# RF1_RS485v5.net
KiCad netlist of a schematic drawn in EAGLE
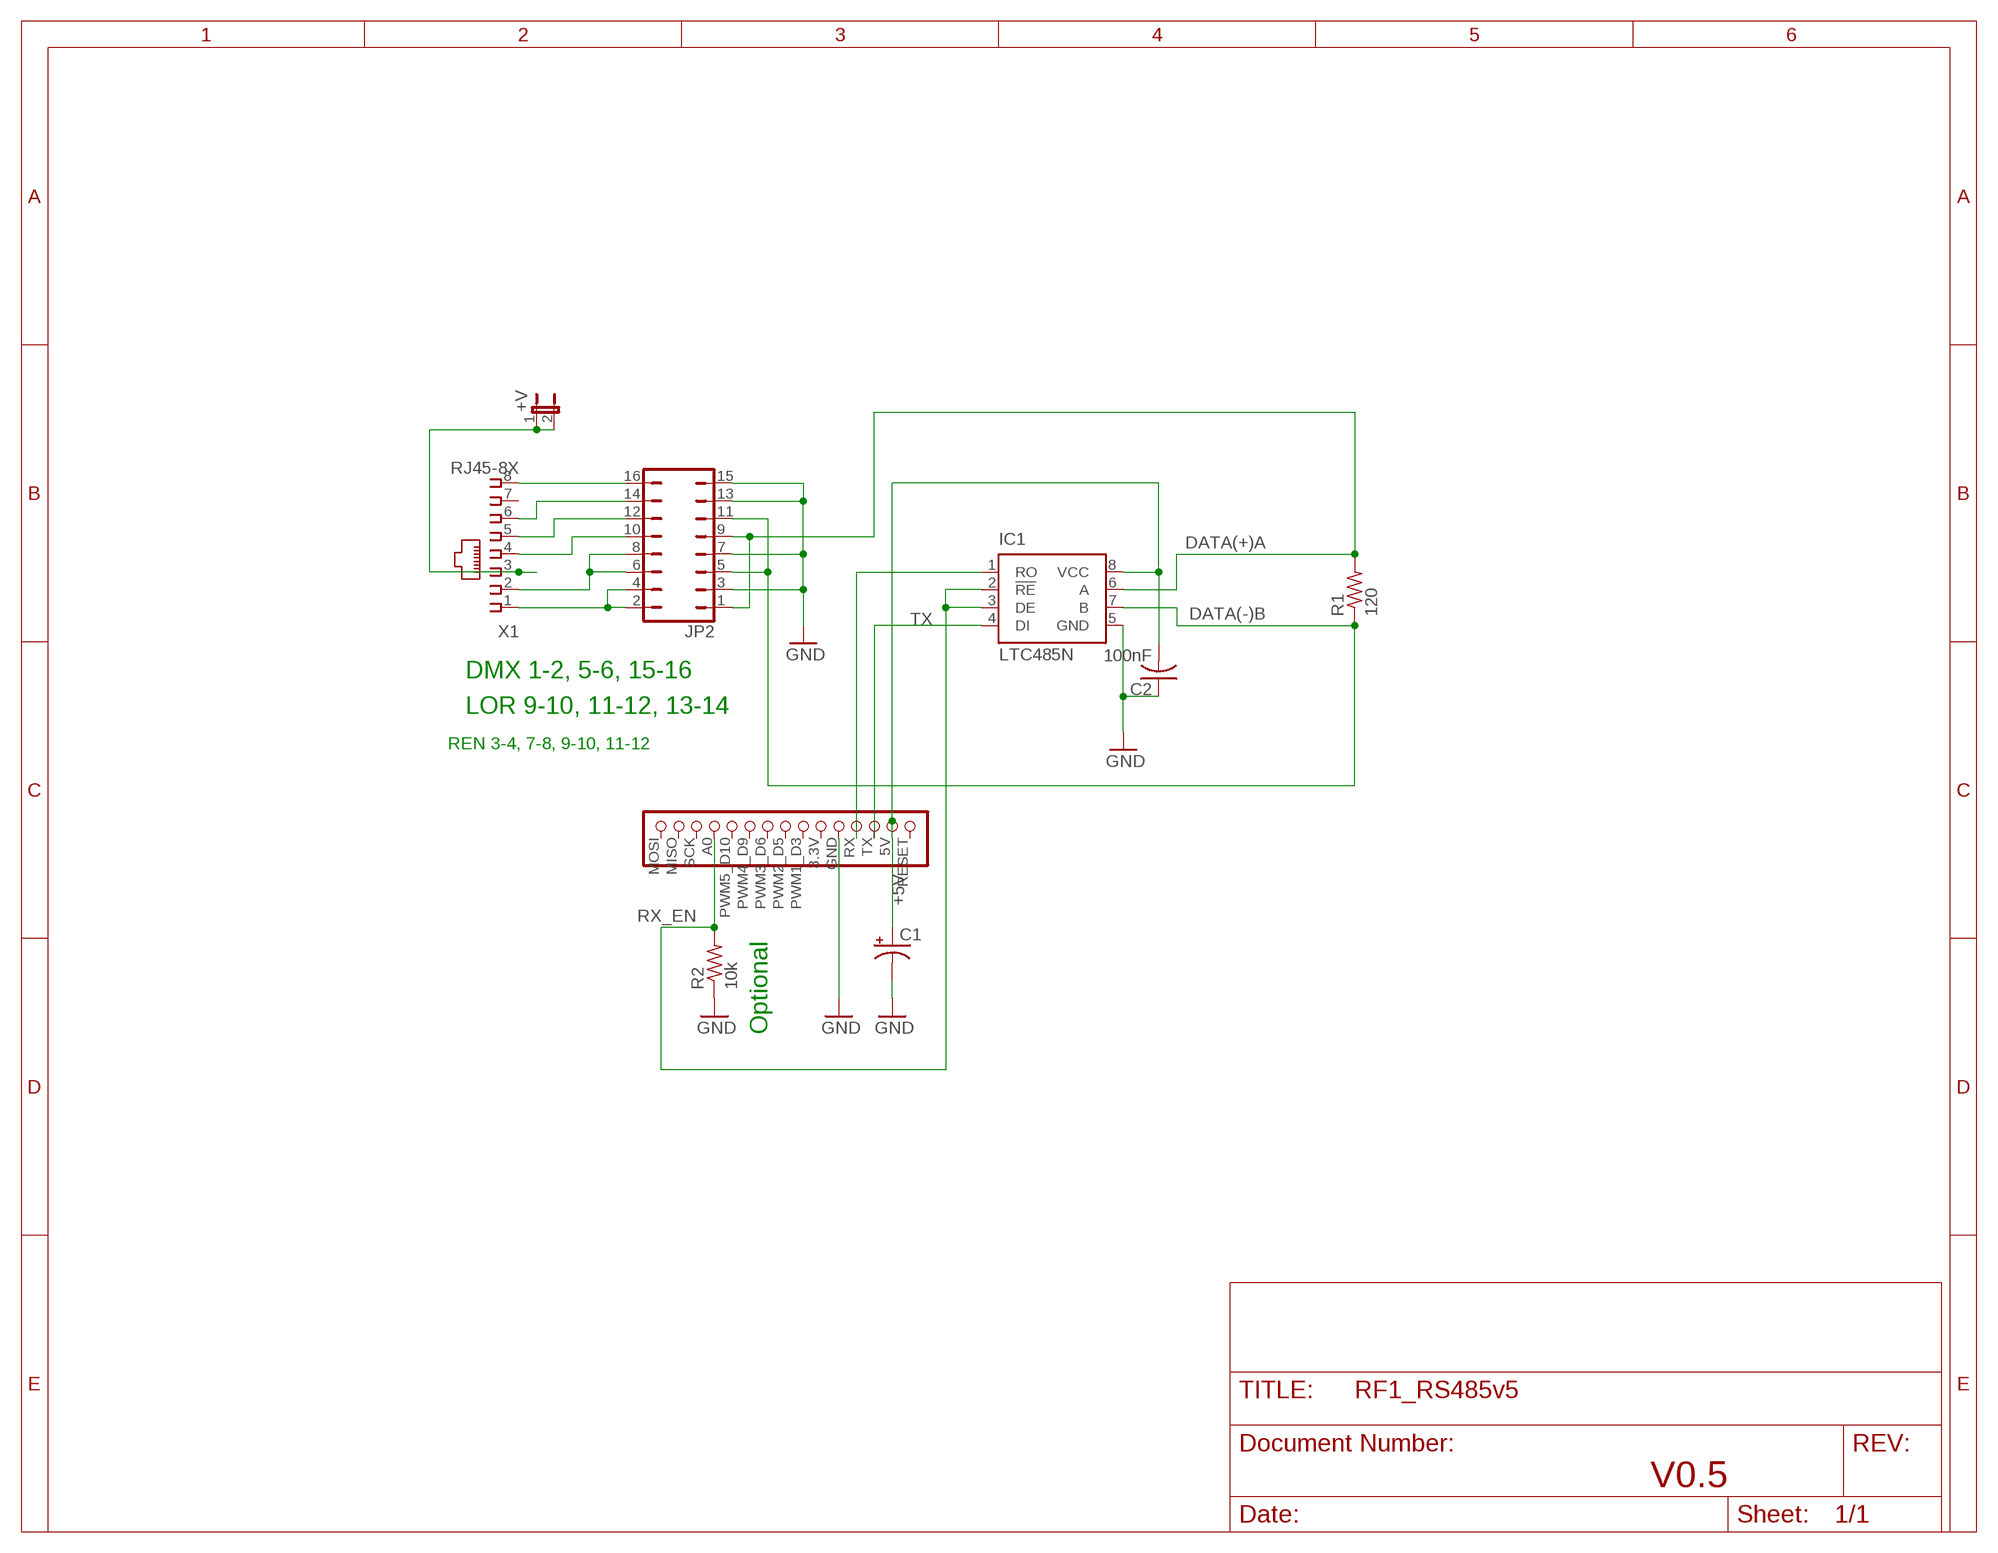
[diagram p0: schematic, sheet 1]

(export (version "E")
  (design (tool "Eeschema 10.0.6"))
  (components
    (comp (ref "+V")
      (value "JP1E")
      (footprint "eagle-import:JP1")
      (libsource (lib "eagle-import") (part "JP1E"))
    )
    (comp (ref "C1")
      (value "CPOL-USE5-5")
      (footprint "eagle-import:E5-5")
      (libsource (lib "eagle-import") (part "CPOL-USE5-5"))
    )
    (comp (ref "C2")
      (value "100nF")
      (footprint "eagle-import:C025-024X044")
      (libsource (lib "eagle-import") (part "C-US025-024X044"))
    )
    (comp (ref "IC1")
      (value "LTC485N")
      (footprint "eagle-import:DIL08")
      (libsource (lib "eagle-import") (part "LTC485N"))
    )
    (comp (ref "JP2")
      (value "JP8Q")
      (footprint "eagle-import:JP8Q")
      (libsource (lib "eagle-import") (part "JP8Q"))
    )
    (comp (ref "R1")
      (value "120")
      (footprint "eagle-import:0805-THM")
      (libsource (lib "eagle-import") (part "R-US_FLIPFLOP"))
    )
    (comp (ref "R2")
      (value "10k")
      (footprint "eagle-import:0805-THM")
      (libsource (lib "eagle-import") (part "R-US_FLIPFLOP"))
    )
    (comp (ref "U$1")
      (value "RF1_HEADER_LEFT")
      (footprint "eagle-import:RF1_LEFTHEADER_ONLY")
      (libsource (lib "eagle-import") (part "RF1_HEADER_LEFT"))
    )
    (comp (ref "X1")
      (value "RJ45-8X")
      (footprint "eagle-import:RJ45-NO-SHIELD")
      (libsource (lib "eagle-import") (part "RJ45-8X"))
    )
  )
  (nets
    (net (code "1") (name "/+5V") (class "Default")
      (node (ref "C1") (pin "+") (pinfunction "+_+") (pintype "passive"))
      (node (ref "C2") (pin "2") (pinfunction "2_2") (pintype "passive"))
      (node (ref "IC1") (pin "8") (pinfunction "VCC_8") (pintype "input"))
      (node (ref "U$1") (pin "5V") (pinfunction "5V_5V") (pintype "passive"))
    )
    (net (code "2") (name "/DATA(+)A") (class "Default")
      (node (ref "IC1") (pin "6") (pinfunction "A_6") (pintype "bidirectional"))
      (node (ref "JP2") (pin "1") (pinfunction "1_1") (pintype "passive"))
      (node (ref "JP2") (pin "9") (pinfunction "9_9") (pintype "passive"))
      (node (ref "R1") (pin "2") (pinfunction "2_2") (pintype "passive"))
    )
    (net (code "3") (name "/DATA(-)B") (class "Default")
      (node (ref "IC1") (pin "7") (pinfunction "B_7") (pintype "bidirectional"))
      (node (ref "JP2") (pin "11") (pinfunction "11_11") (pintype "passive"))
      (node (ref "JP2") (pin "5") (pinfunction "5_5") (pintype "passive"))
      (node (ref "R1") (pin "1") (pinfunction "1_1") (pintype "passive"))
    )
    (net (code "4") (name "/RX_EN") (class "Default")
      (node (ref "IC1") (pin "2") (pinfunction "~{RE}_2") (pintype "input"))
      (node (ref "IC1") (pin "3") (pinfunction "DE_3") (pintype "input"))
      (node (ref "R2") (pin "2") (pinfunction "2_2") (pintype "passive"))
      (node (ref "U$1") (pin "A0") (pinfunction "PC0_A0") (pintype "passive"))
    )
    (net (code "5") (name "/TX") (class "Default")
      (node (ref "IC1") (pin "4") (pinfunction "DI_4") (pintype "input"))
      (node (ref "U$1") (pin "TX") (pinfunction "TX_TX") (pintype "passive"))
    )
    (net (code "6") (name "GND") (class "Default")
      (node (ref "C1") (pin "-") (pinfunction "-_-") (pintype "passive"))
      (node (ref "C2") (pin "1") (pinfunction "1_1") (pintype "passive"))
      (node (ref "IC1") (pin "5") (pinfunction "GND_5") (pintype "input"))
      (node (ref "JP2") (pin "13") (pinfunction "13_13") (pintype "passive"))
      (node (ref "JP2") (pin "15") (pinfunction "15_15") (pintype "passive"))
      (node (ref "JP2") (pin "3") (pinfunction "3_3") (pintype "passive"))
      (node (ref "JP2") (pin "7") (pinfunction "7_7") (pintype "passive"))
      (node (ref "R2") (pin "1") (pinfunction "1_1") (pintype "passive"))
      (node (ref "U$1") (pin "GND") (pinfunction "GND_GND") (pintype "passive"))
    )
    (net (code "7") (name "Net-(+V-Pad1)") (class "Default")
      (node (ref "+V") (pin "1") (pinfunction "1_1") (pintype "passive"))
      (node (ref "+V") (pin "2") (pinfunction "2_2") (pintype "passive"))
      (node (ref "X1") (pin "3") (pinfunction "3_3") (pintype "passive"))
    )
    (net (code "8") (name "Net-(IC1-RO)") (class "Default")
      (node (ref "IC1") (pin "1") (pinfunction "RO_1") (pintype "output"))
      (node (ref "U$1") (pin "RX") (pinfunction "RX_RX") (pintype "passive"))
    )
    (net (code "9") (name "Net-(JP2-Pad2)") (class "Default")
      (node (ref "JP2") (pin "2") (pinfunction "2_2") (pintype "passive"))
      (node (ref "JP2") (pin "4") (pinfunction "4_4") (pintype "passive"))
      (node (ref "X1") (pin "1") (pinfunction "1_1") (pintype "passive"))
    )
    (net (code "10") (name "Net-(JP2-Pad6)") (class "Default")
      (node (ref "JP2") (pin "6") (pinfunction "6_6") (pintype "passive"))
      (node (ref "JP2") (pin "8") (pinfunction "8_8") (pintype "passive"))
      (node (ref "X1") (pin "2") (pinfunction "2_2") (pintype "passive"))
    )
    (net (code "11") (name "Net-(JP2-Pad10)") (class "Default")
      (node (ref "JP2") (pin "10") (pinfunction "10_10") (pintype "passive"))
      (node (ref "X1") (pin "4") (pinfunction "4_4") (pintype "passive"))
    )
    (net (code "12") (name "Net-(JP2-Pad12)") (class "Default")
      (node (ref "JP2") (pin "12") (pinfunction "12_12") (pintype "passive"))
      (node (ref "X1") (pin "5") (pinfunction "5_5") (pintype "passive"))
    )
    (net (code "13") (name "Net-(JP2-Pad14)") (class "Default")
      (node (ref "JP2") (pin "14") (pinfunction "14_14") (pintype "passive"))
      (node (ref "X1") (pin "6") (pinfunction "6_6") (pintype "passive"))
    )
    (net (code "14") (name "Net-(JP2-Pad16)") (class "Default")
      (node (ref "JP2") (pin "16") (pinfunction "16_16") (pintype "passive"))
      (node (ref "X1") (pin "8") (pinfunction "8_8") (pintype "passive"))
    )
    (net (code "15") (name "unconnected-(U$1-PWM1-PadPWM1_D3)") (class "Default")
      (node (ref "U$1") (pin "PWM1_D3") (pinfunction "PWM1_PWM1_D3") (pintype "passive"))
    )
    (net (code "16") (name "unconnected-(U$1-PWM2-PadPWM2_D5)") (class "Default")
      (node (ref "U$1") (pin "PWM2_D5") (pinfunction "PWM2_PWM2_D5") (pintype "passive"))
    )
    (net (code "17") (name "unconnected-(U$1-PWM3-PadPWM3_D6)") (class "Default")
      (node (ref "U$1") (pin "PWM3_D6") (pinfunction "PWM3_PWM3_D6") (pintype "passive"))
    )
    (net (code "18") (name "unconnected-(U$1-PWM4-PadPWM4_D9)") (class "Default")
      (node (ref "U$1") (pin "PWM4_D9") (pinfunction "PWM4_PWM4_D9") (pintype "passive"))
    )
    (net (code "19") (name "unconnected-(U$1-PWM5-PadPWM5_D10)") (class "Default")
      (node (ref "U$1") (pin "PWM5_D10") (pinfunction "PWM5_PWM5_D10") (pintype "passive"))
    )
    (net (code "20") (name "unconnected-(U$1-Pad3.3V)") (class "Default")
      (node (ref "U$1") (pin "3.3V") (pinfunction "3.3V_3.3V") (pintype "passive"))
    )
    (net (code "21") (name "unconnected-(U$1-PadMISO)") (class "Default")
      (node (ref "U$1") (pin "MISO") (pinfunction "MISO_MISO") (pintype "passive"))
    )
    (net (code "22") (name "unconnected-(U$1-PadMOSI)") (class "Default")
      (node (ref "U$1") (pin "MOSI") (pinfunction "MOSI_MOSI") (pintype "passive"))
    )
    (net (code "23") (name "unconnected-(U$1-PadRESET)") (class "Default")
      (node (ref "U$1") (pin "RESET") (pinfunction "RESET_RESET") (pintype "passive"))
    )
    (net (code "24") (name "unconnected-(U$1-PadSCK)") (class "Default")
      (node (ref "U$1") (pin "SCK") (pinfunction "SCK_SCK") (pintype "passive"))
    )
    (net (code "25") (name "unconnected-(X1-Pad7)") (class "Default")
      (node (ref "X1") (pin "7") (pinfunction "7_7") (pintype "passive"))
    )
  )
)
